# FuenteProtoLarga_v11.net
KiCad netlist of a schematic drawn in EAGLE
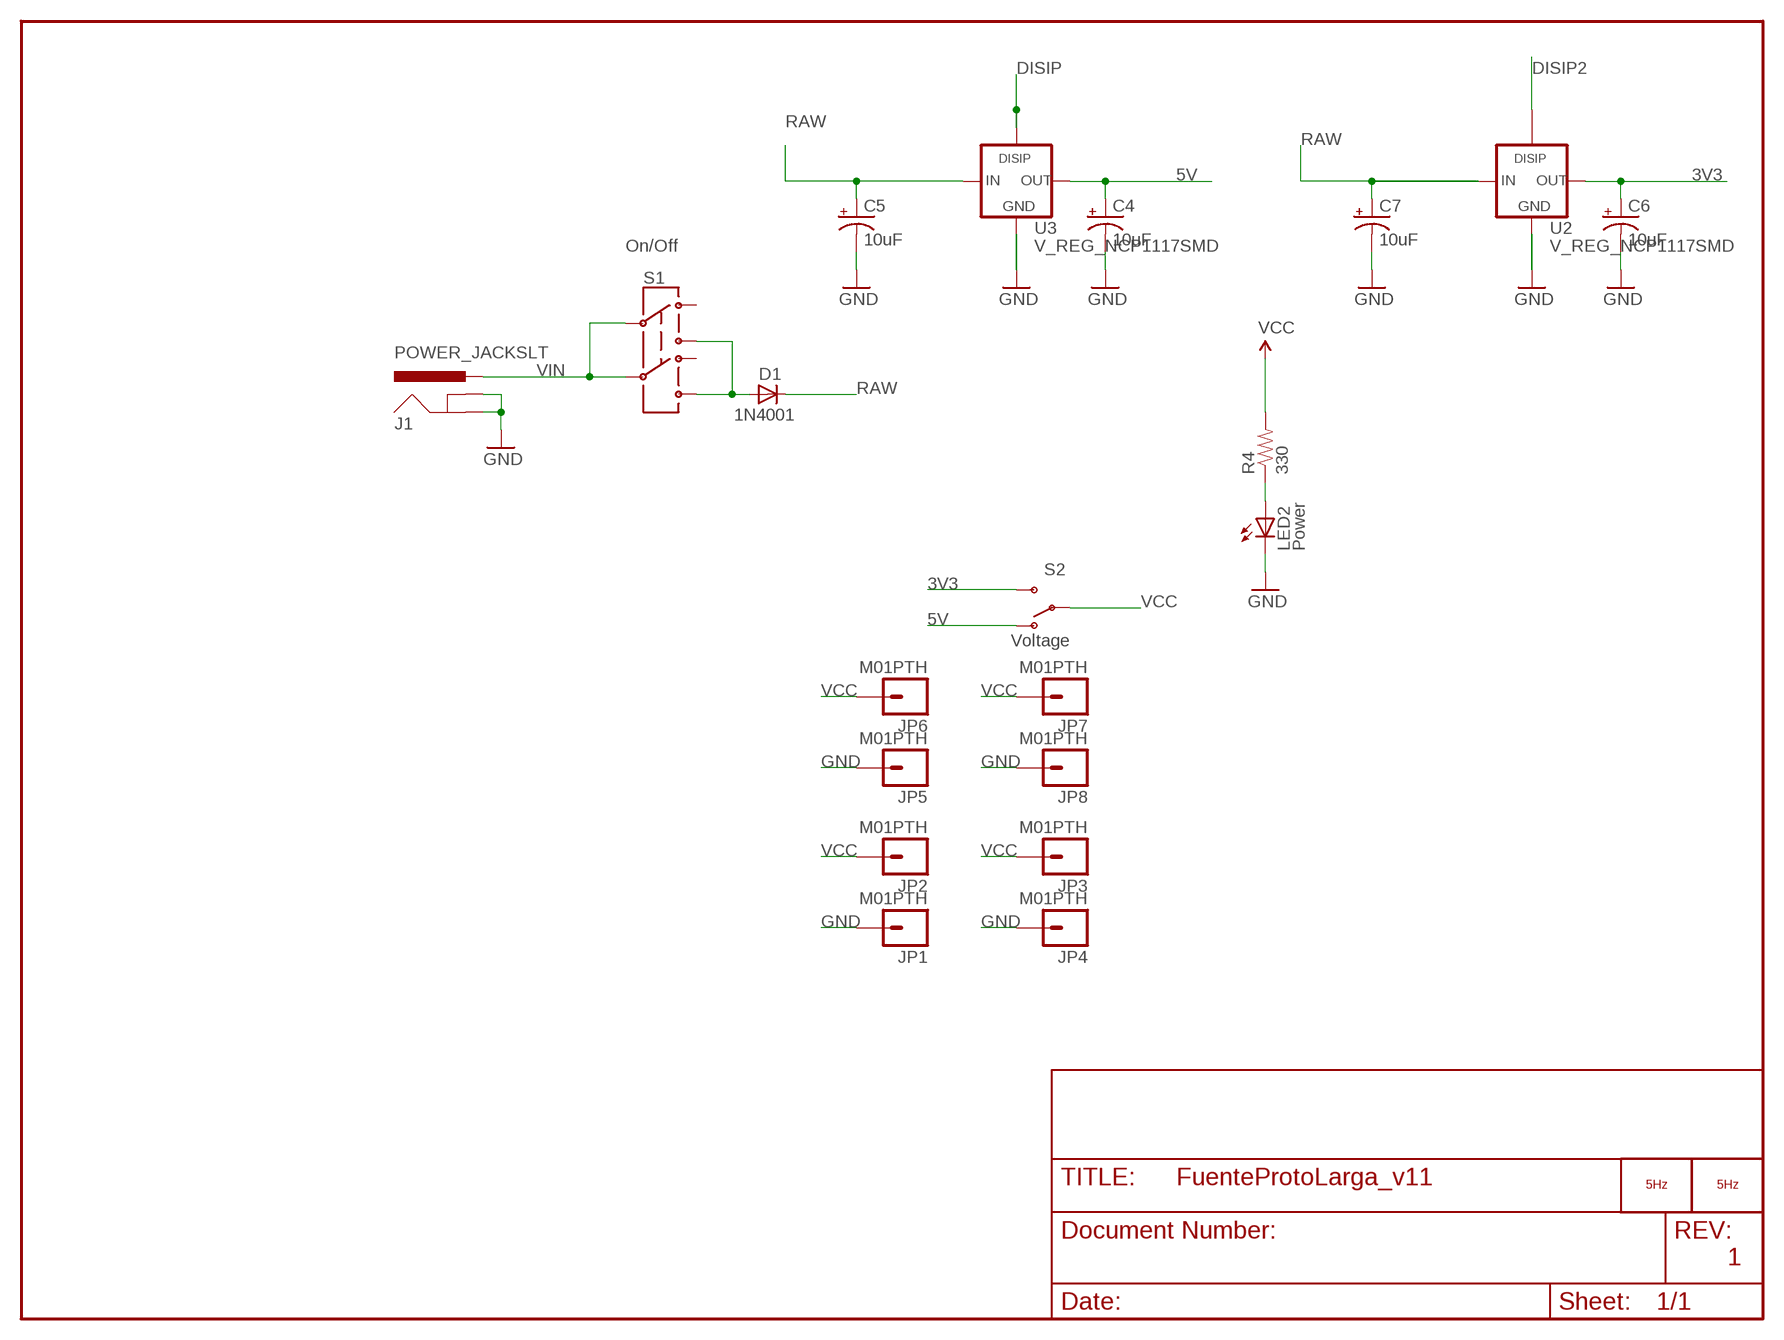
[diagram p0: schematic, sheet 1]

(export (version "E")
  (design (tool "Eeschema 10.0.6"))
  (components
    (comp (ref "C4")
      (value "10uF")
      (footprint "eagle-import:EIA3216")
      (libsource (lib "eagle-import") (part "CAP_POL1206"))
    )
    (comp (ref "C5")
      (value "10uF")
      (footprint "eagle-import:EIA3216")
      (libsource (lib "eagle-import") (part "CAP_POL1206"))
    )
    (comp (ref "C6")
      (value "10uF")
      (footprint "eagle-import:EIA3216")
      (libsource (lib "eagle-import") (part "CAP_POL1206"))
    )
    (comp (ref "C7")
      (value "10uF")
      (footprint "eagle-import:EIA3216")
      (libsource (lib "eagle-import") (part "CAP_POL1206"))
    )
    (comp (ref "D1")
      (value "1N4001")
      (footprint "eagle-import:SMA-DIODE")
      (libsource (lib "eagle-import") (part "DIODESMA"))
    )
    (comp (ref "J1")
      (value "POWER_JACKSLT")
      (footprint "eagle-import:POWER_JACK_SLOT")
      (libsource (lib "eagle-import") (part "POWER_JACKSLT"))
    )
    (comp (ref "JP1")
      (value "M01PTH")
      (footprint "eagle-import:1X01")
      (libsource (lib "eagle-import") (part "M01PTH"))
    )
    (comp (ref "JP2")
      (value "M01PTH")
      (footprint "eagle-import:1X01")
      (libsource (lib "eagle-import") (part "M01PTH"))
    )
    (comp (ref "JP3")
      (value "M01PTH")
      (footprint "eagle-import:1X01")
      (libsource (lib "eagle-import") (part "M01PTH"))
    )
    (comp (ref "JP4")
      (value "M01PTH")
      (footprint "eagle-import:1X01")
      (libsource (lib "eagle-import") (part "M01PTH"))
    )
    (comp (ref "JP5")
      (value "M01PTH")
      (footprint "eagle-import:1X01")
      (libsource (lib "eagle-import") (part "M01PTH"))
    )
    (comp (ref "JP6")
      (value "M01PTH")
      (footprint "eagle-import:1X01")
      (libsource (lib "eagle-import") (part "M01PTH"))
    )
    (comp (ref "JP7")
      (value "M01PTH")
      (footprint "eagle-import:1X01")
      (libsource (lib "eagle-import") (part "M01PTH"))
    )
    (comp (ref "JP8")
      (value "M01PTH")
      (footprint "eagle-import:1X01")
      (libsource (lib "eagle-import") (part "M01PTH"))
    )
    (comp (ref "LED2")
      (value "Power")
      (footprint "eagle-import:LED-0603")
      (libsource (lib "eagle-import") (part "LED0603"))
    )
    (comp (ref "LOGO1")
      (value "LOGO_5HZ_H_10MM")
      (footprint "eagle-import:5HZ_LOGO_H_10MM")
      (libsource (lib "eagle-import") (part "LOGO_5HZ_H_10MM"))
    )
    (comp (ref "LOGO2")
      (value "LOGO_5HZ_H_COOPER_15MM")
      (footprint "eagle-import:5HZ_LOGO_H_COOPER_15MM")
      (libsource (lib "eagle-import") (part "LOGO_5HZ_H_COOPER_15MM"))
    )
    (comp (ref "R4")
      (value "330")
      (footprint "eagle-import:0603-RES")
      (libsource (lib "eagle-import") (part "RESISTOR0603-RES"))
    )
    (comp (ref "S1")
      (value "On/Off")
      (footprint "eagle-import:AYZ0202")
      (libsource (lib "eagle-import") (part "AYZ0202"))
    )
    (comp (ref "S2")
      (value "Voltage")
      (footprint "eagle-import:AYZ0202")
      (libsource (lib "eagle-import") (part "SWITCH-SPSTSMD"))
    )
    (comp (ref "U2")
      (value "V_REG_NCP1117SMD")
      (footprint "eagle-import:SOT223")
      (libsource (lib "eagle-import") (part "V_REG_NCP1117SMD"))
    )
    (comp (ref "U3")
      (value "V_REG_NCP1117SMD")
      (footprint "eagle-import:SOT223")
      (libsource (lib "eagle-import") (part "V_REG_NCP1117SMD"))
    )
  )
  (nets
    (net (code "1") (name "/3V3") (class "Default")
      (node (ref "C6") (pin "A") (pinfunction "+_A") (pintype "passive"))
      (node (ref "S2") (pin "3") (pinfunction "S_3") (pintype "passive"))
      (node (ref "U2") (pin "2") (pinfunction "OUT_2") (pintype "output"))
    )
    (net (code "2") (name "/5V") (class "Default")
      (node (ref "C4") (pin "A") (pinfunction "+_A") (pintype "passive"))
      (node (ref "S2") (pin "1") (pinfunction "O_1") (pintype "passive"))
      (node (ref "U3") (pin "2") (pinfunction "OUT_2") (pintype "output"))
    )
    (net (code "3") (name "/DISIP") (class "Default")
      (node (ref "U3") (pin "4") (pinfunction "P$1_4") (pintype "bidirectional"))
    )
    (net (code "4") (name "/DISIP2") (class "Default")
      (node (ref "U2") (pin "4") (pinfunction "P$1_4") (pintype "bidirectional"))
    )
    (net (code "5") (name "/RAW") (class "Default")
      (node (ref "C5") (pin "A") (pinfunction "+_A") (pintype "passive"))
      (node (ref "C7") (pin "A") (pinfunction "+_A") (pintype "passive"))
      (node (ref "D1") (pin "C") (pinfunction "C_C") (pintype "passive"))
      (node (ref "U2") (pin "3") (pinfunction "IN_3") (pintype "input"))
      (node (ref "U3") (pin "3") (pinfunction "IN_3") (pintype "input"))
    )
    (net (code "6") (name "/VIN") (class "Default")
      (node (ref "J1") (pin "PWR") (pinfunction "PWR_PWR") (pintype "bidirectional"))
      (node (ref "S1") (pin "2") (pinfunction "2_2") (pintype "bidirectional"))
      (node (ref "S1") (pin "5") (pinfunction "5_5") (pintype "bidirectional"))
    )
    (net (code "7") (name "GND") (class "Default")
      (node (ref "C4") (pin "C") (pinfunction "-_C") (pintype "passive"))
      (node (ref "C5") (pin "C") (pinfunction "-_C") (pintype "passive"))
      (node (ref "C6") (pin "C") (pinfunction "-_C") (pintype "passive"))
      (node (ref "C7") (pin "C") (pinfunction "-_C") (pintype "passive"))
      (node (ref "J1") (pin "GND@1") (pinfunction "GNDBREAK_GND@1") (pintype "bidirectional"))
      (node (ref "J1") (pin "GND@2") (pinfunction "GND_GND@2") (pintype "bidirectional"))
      (node (ref "JP1") (pin "1") (pinfunction "1_1") (pintype "passive"))
      (node (ref "JP4") (pin "1") (pinfunction "1_1") (pintype "passive"))
      (node (ref "JP5") (pin "1") (pinfunction "1_1") (pintype "passive"))
      (node (ref "JP8") (pin "1") (pinfunction "1_1") (pintype "passive"))
      (node (ref "LED2") (pin "C") (pinfunction "C_C") (pintype "passive"))
      (node (ref "U2") (pin "1") (pinfunction "GND_1") (pintype "input"))
      (node (ref "U3") (pin "1") (pinfunction "GND_1") (pintype "input"))
    )
    (net (code "8") (name "Net-(LED2-PadA)") (class "Default")
      (node (ref "LED2") (pin "A") (pinfunction "A_A") (pintype "passive"))
      (node (ref "R4") (pin "1") (pinfunction "1_1") (pintype "passive"))
    )
    (net (code "9") (name "Net-(S1-3)") (class "Default")
      (node (ref "D1") (pin "A") (pinfunction "A_A") (pintype "passive"))
      (node (ref "S1") (pin "1") (pinfunction "3_1") (pintype "bidirectional"))
      (node (ref "S1") (pin "4") (pinfunction "6_4") (pintype "bidirectional"))
    )
    (net (code "10") (name "VCC") (class "Default")
      (node (ref "JP2") (pin "1") (pinfunction "1_1") (pintype "passive"))
      (node (ref "JP3") (pin "1") (pinfunction "1_1") (pintype "passive"))
      (node (ref "JP6") (pin "1") (pinfunction "1_1") (pintype "passive"))
      (node (ref "JP7") (pin "1") (pinfunction "1_1") (pintype "passive"))
      (node (ref "R4") (pin "2") (pinfunction "2_2") (pintype "passive"))
      (node (ref "S2") (pin "2") (pinfunction "P_2") (pintype "passive"))
    )
    (net (code "11") (name "unconnected-(S1-1-Pad3)") (class "Default")
      (node (ref "S1") (pin "3") (pinfunction "1_3") (pintype "bidirectional"))
    )
    (net (code "12") (name "unconnected-(S1-4-Pad6)") (class "Default")
      (node (ref "S1") (pin "6") (pinfunction "4_6") (pintype "bidirectional"))
    )
  )
)
